# ECNG3020.net
KiCad netlist of a schematic drawn in EAGLE
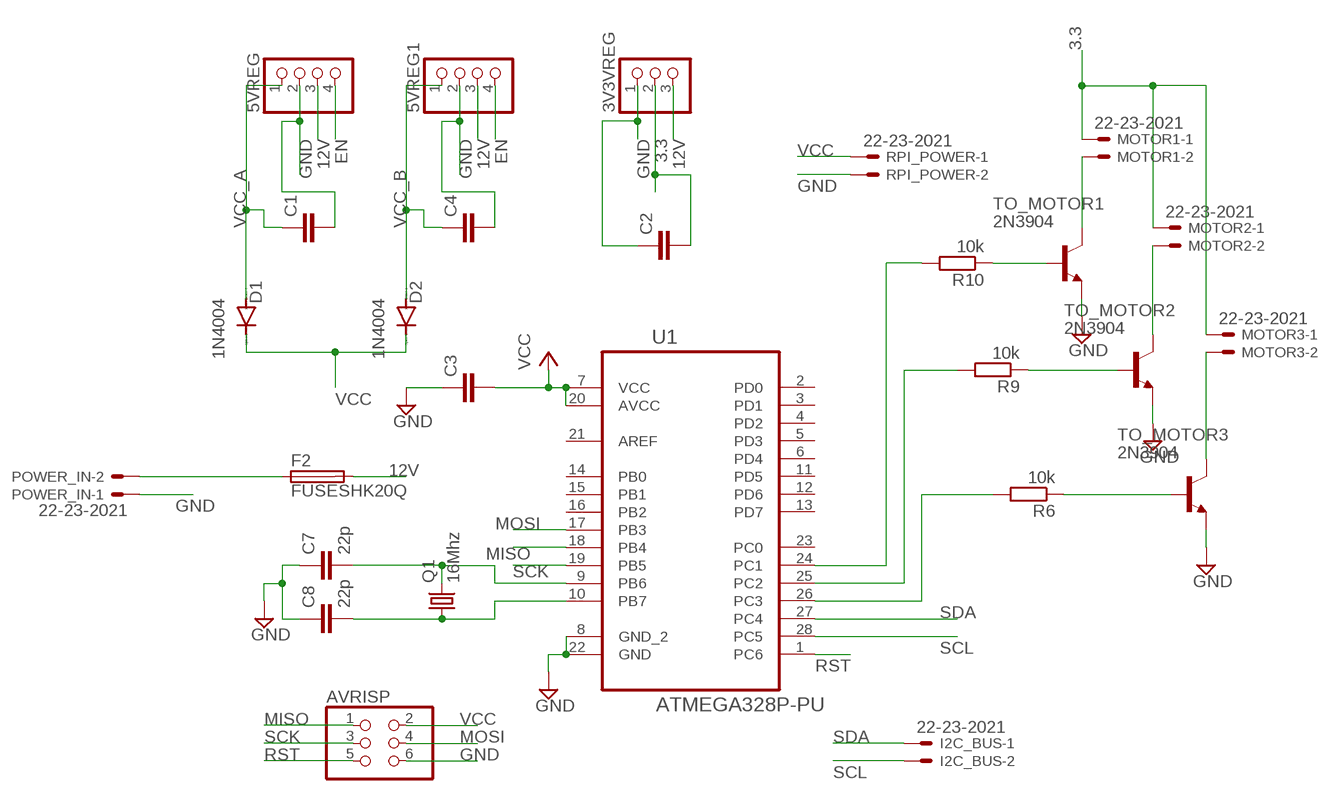
[diagram p0: schematic, sheet 1]

(export (version "E")
  (design (tool "Eeschema 10.0.6"))
  (components
    (comp (ref "3V3VREG")
      (value "PINHD-1X3M")
      (footprint "eagle-import:1X03M")
      (libsource (lib "eagle-import") (part "PINHD-1X3M"))
    )
    (comp (ref "5VREG")
      (value "PINHD-1X4M")
      (footprint "eagle-import:1X04M")
      (libsource (lib "eagle-import") (part "PINHD-1X4M"))
    )
    (comp (ref "5VREG1")
      (value "PINHD-1X4M")
      (footprint "eagle-import:1X04M")
      (libsource (lib "eagle-import") (part "PINHD-1X4M"))
    )
    (comp (ref "AVRISP")
      (value "PINHD-2X3")
      (footprint "eagle-import:2X03")
      (libsource (lib "eagle-import") (part "PINHD-2X3"))
    )
    (comp (ref "C1")
      (value "C2,5-3")
      (footprint "eagle-import:C2.5-3")
      (libsource (lib "eagle-import") (part "C2,5-3"))
    )
    (comp (ref "C2")
      (value "C2,5-3")
      (footprint "eagle-import:C2.5-3")
      (libsource (lib "eagle-import") (part "C2,5-3"))
    )
    (comp (ref "C3")
      (value "C2,5-3")
      (footprint "eagle-import:C2.5-3")
      (libsource (lib "eagle-import") (part "C2,5-3"))
    )
    (comp (ref "C4")
      (value "C2,5-3")
      (footprint "eagle-import:C2.5-3")
      (libsource (lib "eagle-import") (part "C2,5-3"))
    )
    (comp (ref "C7")
      (value "22p")
      (footprint "eagle-import:C050-024X044")
      (libsource (lib "eagle-import") (part "C-EU050-024X044"))
    )
    (comp (ref "C8")
      (value "22p")
      (footprint "eagle-import:C050-024X044")
      (libsource (lib "eagle-import") (part "C-EU050-024X044"))
    )
    (comp (ref "D1")
      (value "1N4004")
      (footprint "eagle-import:DO41-10")
      (libsource (lib "eagle-import") (part "1N4004"))
    )
    (comp (ref "D2")
      (value "1N4004")
      (footprint "eagle-import:DO41-10")
      (libsource (lib "eagle-import") (part "1N4004"))
    )
    (comp (ref "F2")
      (value "FUSESHK20Q")
      (footprint "eagle-import:SHK20Q")
      (libsource (lib "eagle-import") (part "FUSESHK20Q"))
    )
    (comp (ref "I2C_BUS")
      (value "22-23-2021")
      (footprint "eagle-import:22-23-2021")
      (fields (field (name "MF") "MOLEX"))
      (libsource (lib "eagle-import") (part "22-23-2021"))
    )
    (comp (ref "MOTOR1")
      (value "22-23-2021")
      (footprint "eagle-import:22-23-2021")
      (fields (field (name "MF") "MOLEX"))
      (libsource (lib "eagle-import") (part "22-23-2021"))
    )
    (comp (ref "MOTOR2")
      (value "22-23-2021")
      (footprint "eagle-import:22-23-2021")
      (fields (field (name "MF") "MOLEX"))
      (libsource (lib "eagle-import") (part "22-23-2021"))
    )
    (comp (ref "MOTOR3")
      (value "22-23-2021")
      (footprint "eagle-import:22-23-2021")
      (fields (field (name "MF") "MOLEX"))
      (libsource (lib "eagle-import") (part "22-23-2021"))
    )
    (comp (ref "POWER_IN")
      (value "22-23-2021")
      (footprint "eagle-import:22-23-2021")
      (fields (field (name "MF") "MOLEX"))
      (libsource (lib "eagle-import") (part "22-23-2021"))
    )
    (comp (ref "Q1")
      (value "16Mhz")
      (footprint "eagle-import:HC49_S")
      (libsource (lib "eagle-import") (part "CRYSTALHC49S"))
    )
    (comp (ref "R6")
      (value "10k")
      (footprint "eagle-import:0207_10")
      (libsource (lib "eagle-import") (part "R-EU_0207/10"))
    )
    (comp (ref "R9")
      (value "10k")
      (footprint "eagle-import:0207_10")
      (libsource (lib "eagle-import") (part "R-EU_0207/10"))
    )
    (comp (ref "R10")
      (value "10k")
      (footprint "eagle-import:0207_10")
      (libsource (lib "eagle-import") (part "R-EU_0207/10"))
    )
    (comp (ref "RPI_POWER")
      (value "22-23-2021")
      (footprint "eagle-import:22-23-2021")
      (fields (field (name "MF") "MOLEX"))
      (libsource (lib "eagle-import") (part "22-23-2021"))
    )
    (comp (ref "TO_MOTOR1")
      (value "2N3904")
      (footprint "eagle-import:TO92")
      (libsource (lib "eagle-import") (part "2N3904"))
    )
    (comp (ref "TO_MOTOR2")
      (value "2N3904")
      (footprint "eagle-import:TO92")
      (libsource (lib "eagle-import") (part "2N3904"))
    )
    (comp (ref "TO_MOTOR3")
      (value "2N3904")
      (footprint "eagle-import:TO92")
      (libsource (lib "eagle-import") (part "2N3904"))
    )
    (comp (ref "U1")
      (value "ATMEGA328P-PU")
      (footprint "eagle-import:DIP254P762X457-28")
      (fields (field (name "MF") "Microchip"))
      (libsource (lib "eagle-import") (part "ATMEGA328P-PU"))
    )
  )
  (nets
    (net (code "1") (name "/3.3") (class "Default")
      (node (ref "3V3VREG") (pin "2") (pinfunction "2_2") (pintype "passive"))
      (node (ref "C2") (pin "2") (pinfunction "2_2") (pintype "passive"))
      (node (ref "MOTOR1") (pin "1") (pinfunction "S_1") (pintype "passive"))
      (node (ref "MOTOR2") (pin "1") (pinfunction "S_1") (pintype "passive"))
      (node (ref "MOTOR3") (pin "1") (pinfunction "S_1") (pintype "passive"))
    )
    (net (code "2") (name "/12V") (class "Default")
      (node (ref "3V3VREG") (pin "3") (pinfunction "3_3") (pintype "passive"))
      (node (ref "5VREG") (pin "3") (pinfunction "3_3") (pintype "passive"))
      (node (ref "5VREG1") (pin "3") (pinfunction "3_3") (pintype "passive"))
      (node (ref "F2") (pin "2A") (pinfunction "2_2A") (pintype "passive"))
    )
    (net (code "3") (name "/EN") (class "Default")
      (node (ref "5VREG") (pin "4") (pinfunction "4_4") (pintype "passive"))
      (node (ref "5VREG1") (pin "4") (pinfunction "4_4") (pintype "passive"))
    )
    (net (code "4") (name "/MISO") (class "Default")
      (node (ref "AVRISP") (pin "1") (pinfunction "1_1") (pintype "passive"))
      (node (ref "U1") (pin "18") (pinfunction "PB4_18") (pintype "bidirectional"))
    )
    (net (code "5") (name "/MOSI") (class "Default")
      (node (ref "AVRISP") (pin "4") (pinfunction "4_4") (pintype "passive"))
      (node (ref "U1") (pin "17") (pinfunction "PB3_17") (pintype "bidirectional"))
    )
    (net (code "6") (name "/RST") (class "Default")
      (node (ref "AVRISP") (pin "5") (pinfunction "5_5") (pintype "passive"))
      (node (ref "U1") (pin "1") (pinfunction "PC6_1") (pintype "bidirectional"))
    )
    (net (code "7") (name "/SCK") (class "Default")
      (node (ref "AVRISP") (pin "3") (pinfunction "3_3") (pintype "passive"))
      (node (ref "U1") (pin "19") (pinfunction "PB5_19") (pintype "bidirectional"))
    )
    (net (code "8") (name "/SCL") (class "Default")
      (node (ref "I2C_BUS") (pin "2") (pinfunction "S_2") (pintype "passive"))
      (node (ref "U1") (pin "28") (pinfunction "PC5_28") (pintype "bidirectional"))
    )
    (net (code "9") (name "/SDA") (class "Default")
      (node (ref "I2C_BUS") (pin "1") (pinfunction "S_1") (pintype "passive"))
      (node (ref "U1") (pin "27") (pinfunction "PC4_27") (pintype "bidirectional"))
    )
    (net (code "10") (name "/VCC_A") (class "Default")
      (node (ref "5VREG") (pin "1") (pinfunction "1_1") (pintype "passive"))
      (node (ref "C1") (pin "1") (pinfunction "1_1") (pintype "passive"))
      (node (ref "D1") (pin "A") (pinfunction "A_A") (pintype "passive"))
    )
    (net (code "11") (name "/VCC_B") (class "Default")
      (node (ref "5VREG1") (pin "1") (pinfunction "1_1") (pintype "passive"))
      (node (ref "C4") (pin "1") (pinfunction "1_1") (pintype "passive"))
      (node (ref "D2") (pin "A") (pinfunction "A_A") (pintype "passive"))
    )
    (net (code "12") (name "GND") (class "Default")
      (node (ref "3V3VREG") (pin "1") (pinfunction "1_1") (pintype "passive"))
      (node (ref "5VREG") (pin "2") (pinfunction "2_2") (pintype "passive"))
      (node (ref "5VREG1") (pin "2") (pinfunction "2_2") (pintype "passive"))
      (node (ref "AVRISP") (pin "6") (pinfunction "6_6") (pintype "passive"))
      (node (ref "C1") (pin "2") (pinfunction "2_2") (pintype "passive"))
      (node (ref "C2") (pin "1") (pinfunction "1_1") (pintype "passive"))
      (node (ref "C3") (pin "1") (pinfunction "1_1") (pintype "passive"))
      (node (ref "C4") (pin "2") (pinfunction "2_2") (pintype "passive"))
      (node (ref "C7") (pin "1") (pinfunction "1_1") (pintype "passive"))
      (node (ref "C8") (pin "1") (pinfunction "1_1") (pintype "passive"))
      (node (ref "POWER_IN") (pin "1") (pinfunction "S_1") (pintype "passive"))
      (node (ref "RPI_POWER") (pin "2") (pinfunction "S_2") (pintype "passive"))
      (node (ref "TO_MOTOR1") (pin "3") (pinfunction "E_3") (pintype "passive"))
      (node (ref "TO_MOTOR2") (pin "3") (pinfunction "E_3") (pintype "passive"))
      (node (ref "TO_MOTOR3") (pin "3") (pinfunction "E_3") (pintype "passive"))
      (node (ref "U1") (pin "22") (pinfunction "GND_22") (pintype "passive"))
      (node (ref "U1") (pin "8") (pinfunction "GND_2_8") (pintype "passive"))
    )
    (net (code "13") (name "Net-(F2-1)") (class "Default")
      (node (ref "F2") (pin "1A") (pinfunction "1_1A") (pintype "passive"))
      (node (ref "POWER_IN") (pin "2") (pinfunction "S_2") (pintype "passive"))
    )
    (net (code "14") (name "Net-(MOTOR1B-S)") (class "Default")
      (node (ref "MOTOR1") (pin "2") (pinfunction "S_2") (pintype "passive"))
      (node (ref "TO_MOTOR1") (pin "1") (pinfunction "C_1") (pintype "passive"))
    )
    (net (code "15") (name "Net-(MOTOR2B-S)") (class "Default")
      (node (ref "MOTOR2") (pin "2") (pinfunction "S_2") (pintype "passive"))
      (node (ref "TO_MOTOR2") (pin "1") (pinfunction "C_1") (pintype "passive"))
    )
    (net (code "16") (name "Net-(MOTOR3B-S)") (class "Default")
      (node (ref "MOTOR3") (pin "2") (pinfunction "S_2") (pintype "passive"))
      (node (ref "TO_MOTOR3") (pin "1") (pinfunction "C_1") (pintype "passive"))
    )
    (net (code "17") (name "Net-(TO_MOTOR1-B)") (class "Default")
      (node (ref "R10") (pin "1") (pinfunction "1_1") (pintype "passive"))
      (node (ref "TO_MOTOR1") (pin "2") (pinfunction "B_2") (pintype "passive"))
    )
    (net (code "18") (name "Net-(TO_MOTOR2-B)") (class "Default")
      (node (ref "R9") (pin "1") (pinfunction "1_1") (pintype "passive"))
      (node (ref "TO_MOTOR2") (pin "2") (pinfunction "B_2") (pintype "passive"))
    )
    (net (code "19") (name "Net-(TO_MOTOR3-B)") (class "Default")
      (node (ref "R6") (pin "1") (pinfunction "1_1") (pintype "passive"))
      (node (ref "TO_MOTOR3") (pin "2") (pinfunction "B_2") (pintype "passive"))
    )
    (net (code "20") (name "Net-(U1-PB6)") (class "Default")
      (node (ref "C7") (pin "2") (pinfunction "2_2") (pintype "passive"))
      (node (ref "Q1") (pin "2") (pinfunction "2_2") (pintype "passive"))
      (node (ref "U1") (pin "9") (pinfunction "PB6_9") (pintype "bidirectional"))
    )
    (net (code "21") (name "Net-(U1-PB7)") (class "Default")
      (node (ref "C8") (pin "2") (pinfunction "2_2") (pintype "passive"))
      (node (ref "Q1") (pin "1") (pinfunction "1_1") (pintype "passive"))
      (node (ref "U1") (pin "10") (pinfunction "PB7_10") (pintype "bidirectional"))
    )
    (net (code "22") (name "Net-(U1-PC1)") (class "Default")
      (node (ref "R10") (pin "2") (pinfunction "2_2") (pintype "passive"))
      (node (ref "U1") (pin "24") (pinfunction "PC1_24") (pintype "bidirectional"))
    )
    (net (code "23") (name "Net-(U1-PC2)") (class "Default")
      (node (ref "R9") (pin "2") (pinfunction "2_2") (pintype "passive"))
      (node (ref "U1") (pin "25") (pinfunction "PC2_25") (pintype "bidirectional"))
    )
    (net (code "24") (name "Net-(U1-PC3)") (class "Default")
      (node (ref "R6") (pin "2") (pinfunction "2_2") (pintype "passive"))
      (node (ref "U1") (pin "26") (pinfunction "PC3_26") (pintype "bidirectional"))
    )
    (net (code "25") (name "VCC") (class "Default")
      (node (ref "AVRISP") (pin "2") (pinfunction "2_2") (pintype "passive"))
      (node (ref "C3") (pin "2") (pinfunction "2_2") (pintype "passive"))
      (node (ref "D1") (pin "C") (pinfunction "C_C") (pintype "passive"))
      (node (ref "D2") (pin "C") (pinfunction "C_C") (pintype "passive"))
      (node (ref "RPI_POWER") (pin "1") (pinfunction "S_1") (pintype "passive"))
      (node (ref "U1") (pin "20") (pinfunction "AVCC_20") (pintype "power_in"))
      (node (ref "U1") (pin "7") (pinfunction "VCC_7") (pintype "power_in"))
    )
    (net (code "26") (name "unconnected-(U1-AREF-Pad21)") (class "Default")
      (node (ref "U1") (pin "21") (pinfunction "AREF_21") (pintype "input"))
    )
    (net (code "27") (name "unconnected-(U1-PB0-Pad14)") (class "Default")
      (node (ref "U1") (pin "14") (pinfunction "PB0_14") (pintype "bidirectional"))
    )
    (net (code "28") (name "unconnected-(U1-PB1-Pad15)") (class "Default")
      (node (ref "U1") (pin "15") (pinfunction "PB1_15") (pintype "bidirectional"))
    )
    (net (code "29") (name "unconnected-(U1-PB2-Pad16)") (class "Default")
      (node (ref "U1") (pin "16") (pinfunction "PB2_16") (pintype "bidirectional"))
    )
    (net (code "30") (name "unconnected-(U1-PC0-Pad23)") (class "Default")
      (node (ref "U1") (pin "23") (pinfunction "PC0_23") (pintype "bidirectional"))
    )
    (net (code "31") (name "unconnected-(U1-PD0-Pad2)") (class "Default")
      (node (ref "U1") (pin "2") (pinfunction "PD0_2") (pintype "bidirectional"))
    )
    (net (code "32") (name "unconnected-(U1-PD1-Pad3)") (class "Default")
      (node (ref "U1") (pin "3") (pinfunction "PD1_3") (pintype "bidirectional"))
    )
    (net (code "33") (name "unconnected-(U1-PD2-Pad4)") (class "Default")
      (node (ref "U1") (pin "4") (pinfunction "PD2_4") (pintype "bidirectional"))
    )
    (net (code "34") (name "unconnected-(U1-PD3-Pad5)") (class "Default")
      (node (ref "U1") (pin "5") (pinfunction "PD3_5") (pintype "bidirectional"))
    )
    (net (code "35") (name "unconnected-(U1-PD4-Pad6)") (class "Default")
      (node (ref "U1") (pin "6") (pinfunction "PD4_6") (pintype "bidirectional"))
    )
    (net (code "36") (name "unconnected-(U1-PD5-Pad11)") (class "Default")
      (node (ref "U1") (pin "11") (pinfunction "PD5_11") (pintype "bidirectional"))
    )
    (net (code "37") (name "unconnected-(U1-PD6-Pad12)") (class "Default")
      (node (ref "U1") (pin "12") (pinfunction "PD6_12") (pintype "bidirectional"))
    )
    (net (code "38") (name "unconnected-(U1-PD7-Pad13)") (class "Default")
      (node (ref "U1") (pin "13") (pinfunction "PD7_13") (pintype "bidirectional"))
    )
  )
)
